# Power.net
KiCad netlist of a schematic drawn in Altium Designer
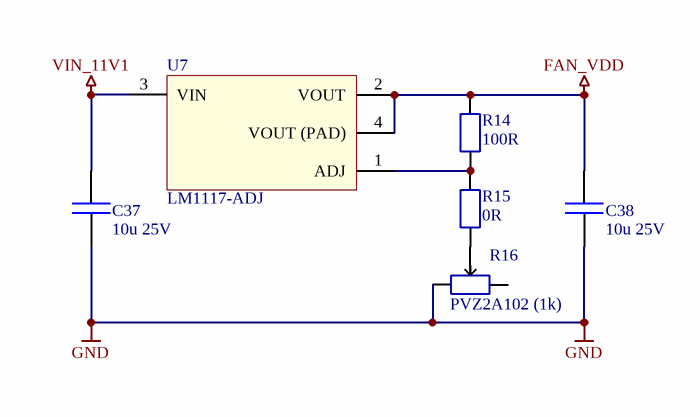
[diagram p0: Power.SchDoc]

(export (version "E")
  (design (tool "Eeschema 10.0.6"))
  (components
    (comp (ref "C37")
      (value "10u 25V")
      (footprint "C_1206/3216")
      (description "Non-polarized capacitor")
      (libsource (lib "passive") (part "Capacitor"))
    )
    (comp (ref "C38")
      (value "10u 25V")
      (footprint "C_1206/3216")
      (description "Non-polarized capacitor")
      (libsource (lib "passive") (part "Capacitor"))
    )
    (comp (ref "R14")
      (value "100R")
      (footprint "R_0603/1608")
      (description "Resistor")
      (libsource (lib "passive") (part "Resistor"))
    )
    (comp (ref "R15")
      (value "0R")
      (footprint "R_0603/1608")
      (description "Resistor")
      (libsource (lib "passive") (part "Resistor"))
    )
    (comp (ref "R16")
      (value "PVZ2A102 (1k)")
      (footprint "R_VAR_3.2x3.2_SMD")
      (description "Resistor variable")
      (libsource (lib "passive") (part "Resistor variable"))
    )
    (comp (ref "U7")
      (value "LM1117-ADJ")
      (footprint "SOT223")
      (description "LDO voltage regulator")
      (libsource (lib "power") (part "LM1117-ADJ"))
    )
  )
  (nets
    (net (code "1") (name "FAN_VDD") (class "Default")
      (node (ref "C38") (pin "1") (pintype "passive"))
      (node (ref "R14") (pin "2") (pintype "passive"))
      (node (ref "U7") (pin "2") (pinfunction "VOUT_2") (pintype "power_in"))
      (node (ref "U7") (pin "4") (pinfunction "VOUT_(PAD)_4") (pintype "power_in"))
    )
    (net (code "2") (name "GND") (class "Default")
      (node (ref "C37") (pin "2") (pintype "passive"))
      (node (ref "C38") (pin "2") (pintype "passive"))
      (node (ref "R16") (pin "1") (pintype "passive"))
    )
    (net (code "3") (name "Net-(R15-Pad1)") (class "Default")
      (node (ref "R15") (pin "1") (pintype "passive"))
      (node (ref "R16") (pin "2") (pintype "passive"))
    )
    (net (code "4") (name "Net-(U7-ADJ)") (class "Default")
      (node (ref "R14") (pin "1") (pintype "passive"))
      (node (ref "R15") (pin "2") (pintype "passive"))
      (node (ref "U7") (pin "1") (pinfunction "ADJ_1") (pintype "power_in"))
    )
    (net (code "5") (name "VIN_11V1") (class "Default")
      (node (ref "C37") (pin "1") (pintype "passive"))
      (node (ref "U7") (pin "3") (pinfunction "VIN_3") (pintype "power_in"))
    )
    (net (code "6") (name "unconnected-(R16-Pad3)") (class "Default")
      (node (ref "R16") (pin "3") (pintype "passive"))
    )
  )
)
